# cpu.net
KiCad netlist of a schematic drawn in Altium Designer
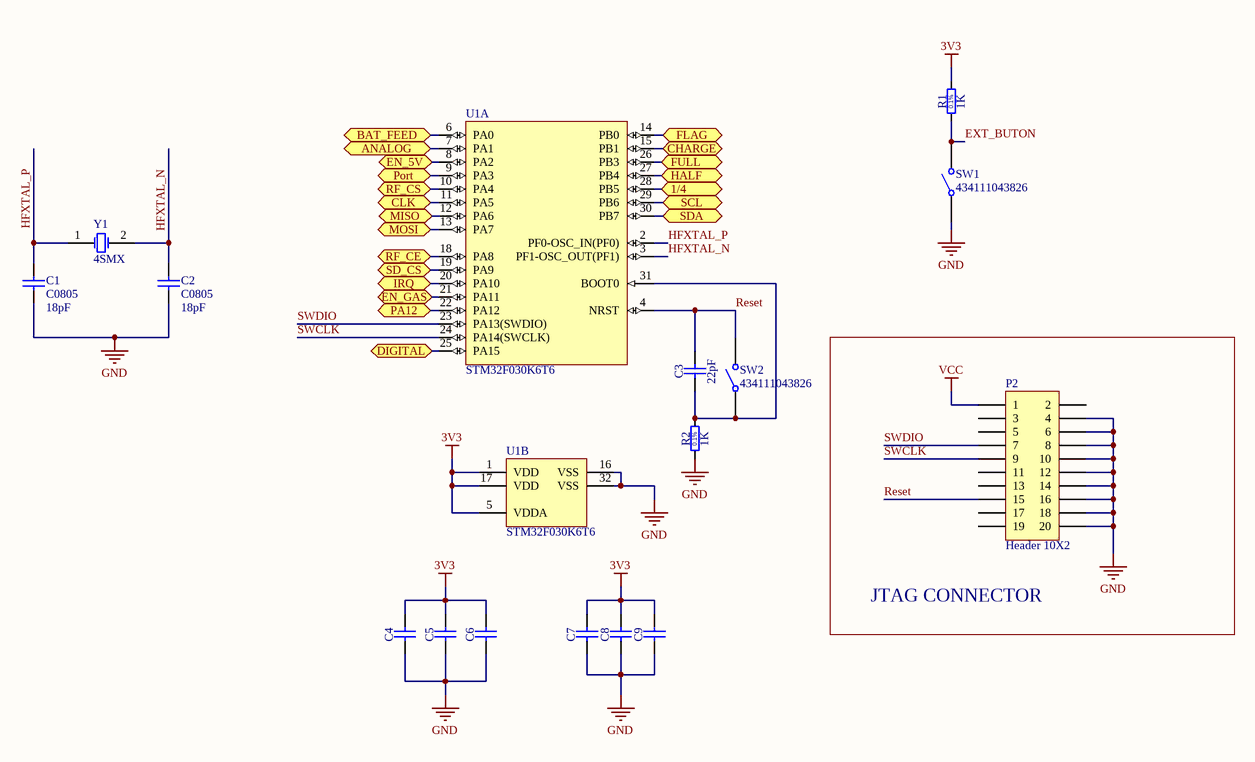
[diagram p0: cpu.SchDoc]

(export (version "E")
  (design (tool "Eeschema 10.0.6"))
  (components
    (comp (ref "C1")
      (value "C0805")
      (footprint "0805")
      (description "Ceramic Chip Capacitor - Standard")
      (fields (field (name "ALTIUM_VALUE") "18pF") (field (name "PUBLISHER") "Altium Limited"))
      (libsource (lib "KEMET Chip Capacitor") (part "C0805"))
    )
    (comp (ref "C2")
      (value "C0805")
      (footprint "0805")
      (description "Ceramic Chip Capacitor - Standard")
      (fields (field (name "ALTIUM_VALUE") "18pF") (field (name "PUBLISHER") "Altium Limited"))
      (libsource (lib "KEMET Chip Capacitor") (part "C0805"))
    )
    (comp (ref "C3")
      (value "22pF")
      (footprint "CAPC2012X135N")
      (description "Non-polarised capacitor")
      (fields
        (field (name "PART NUMBER") "CC0805_10NF_50V_10%_X7R")
        (field (name "VOLTAGE") "50V")
        (field (name "AUTHOR") "CERN DEM JLC")
      )
      (libsource (lib "Capacitors") (part "Capacitor - non polarized"))
    )
    (comp (ref "C4")
      (value "100nF")
      (footprint "CAPC2012X135N")
      (description "Non-polarised capacitor")
      (fields
        (field (name "PART NUMBER") "CC0805_1NF_50V_5%_X7R")
        (field (name "VOLTAGE") "50V")
        (field (name "AUTHOR") "CERN DEM JLC")
      )
      (libsource (lib "Capacitors") (part "Capacitor - non polarized"))
    )
    (comp (ref "C5")
      (value "100nF")
      (footprint "CAPC2012X135N")
      (description "Non-polarised capacitor")
      (fields
        (field (name "PART NUMBER") "CC0805_1NF_50V_5%_X7R")
        (field (name "VOLTAGE") "50V")
        (field (name "AUTHOR") "CERN DEM JLC")
      )
      (libsource (lib "Capacitors") (part "Capacitor - non polarized"))
    )
    (comp (ref "C6")
      (value "100nF")
      (footprint "CAPC2012X135N")
      (description "Non-polarised capacitor")
      (fields
        (field (name "PART NUMBER") "CC0805_1NF_50V_5%_X7R")
        (field (name "VOLTAGE") "50V")
        (field (name "AUTHOR") "CERN DEM JLC")
      )
      (libsource (lib "Capacitors") (part "Capacitor - non polarized"))
    )
    (comp (ref "C7")
      (value "100nF")
      (footprint "CAPC2012X135N")
      (description "Non-polarised capacitor")
      (fields
        (field (name "PART NUMBER") "CC0805_1NF_50V_5%_X7R")
        (field (name "VOLTAGE") "50V")
        (field (name "AUTHOR") "CERN DEM JLC")
      )
      (libsource (lib "Capacitors") (part "Capacitor - non polarized"))
    )
    (comp (ref "C8")
      (value "100nF")
      (footprint "CAPC2012X135N")
      (description "Non-polarised capacitor")
      (fields
        (field (name "PART NUMBER") "CC0805_1NF_50V_5%_X7R")
        (field (name "VOLTAGE") "50V")
        (field (name "AUTHOR") "CERN DEM JLC")
      )
      (libsource (lib "Capacitors") (part "Capacitor - non polarized"))
    )
    (comp (ref "C9")
      (value "100nF")
      (footprint "CAPC2012X135N")
      (description "Non-polarised capacitor")
      (fields
        (field (name "PART NUMBER") "CC0805_1NF_50V_5%_X7R")
        (field (name "VOLTAGE") "50V")
        (field (name "AUTHOR") "CERN DEM JLC")
      )
      (libsource (lib "Capacitors") (part "Capacitor - non polarized"))
    )
    (comp (ref "P2")
      (value "Header 10X2")
      (footprint "HDR2X10")
      (description "Header, 10-Pin, Dual row")
      (fields (field (name "PUBLISHER") "Altium Limited"))
      (libsource (lib "Miscellaneous Connectors") (part "Header 10X2"))
    )
    (comp (ref "R1")
      (value "1K")
      (footprint "RESC2012X60N")
      (description "Resistor - 0.1%")
      (fields
        (field (name "PART NUMBER") "R0805_1K1_0.1%_0.1W_10PPM")
        (field (name "POWER") "0.1W")
        (field (name "AUTHOR") "CERN DEM JLC")
      )
      (libsource (lib "Resistors") (part "Resistor - 0.1%"))
    )
    (comp (ref "R2")
      (value "1K")
      (footprint "RESC2012X60N")
      (description "Resistor - 0.1%")
      (fields
        (field (name "PART NUMBER") "R0805_1K1_0.1%_0.1W_10PPM")
        (field (name "POWER") "0.1W")
        (field (name "AUTHOR") "CERN DEM JLC")
      )
      (libsource (lib "Resistors") (part "Resistor - 0.1%"))
    )
    (comp (ref "SW1")
      (value "434111043826")
      (footprint "434111043826")
      (description "WS-TASV SMD Tact Switch 6.0X3.5 mm")
      (libsource (lib "WS-TASV SMD Tact Switch 6.0X3.5 mm") (part "434111043826"))
    )
    (comp (ref "SW2")
      (value "434111043826")
      (footprint "434111043826")
      (description "WS-TASV SMD Tact Switch 6.0X3.5 mm")
      (libsource (lib "WS-TASV SMD Tact Switch 6.0X3.5 mm") (part "434111043826"))
    )
    (comp (ref "U1")
      (value "STM32F030K6T6")
      (footprint "STM-LQFP32_N")
      (libsource (lib "STMicroelectronics STM32 F0") (part "STM32F030K6T6"))
    )
    (comp (ref "Y1")
      (value "4SMX")
      (footprint "4SMX")
      (description "Surface Mount Quartz Crystal")
      (fields (field (name "PUBLISHER") "Altium Limited"))
      (libsource (lib "C-MAC Crystal Oscillator") (part "4SMX"))
    )
  )
  (nets
    (net (code "1") (name "/1{slash}4") (class "Default")
      (node (ref "U1") (pin "28") (pinfunction "PB5_28") (pintype "bidirectional"))
    )
    (net (code "2") (name "/ANALOG") (class "Default")
      (node (ref "U1") (pin "7") (pinfunction "PA1_7") (pintype "bidirectional"))
    )
    (net (code "3") (name "/BAT_FEED") (class "Default")
      (node (ref "U1") (pin "6") (pinfunction "PA0_6") (pintype "bidirectional"))
    )
    (net (code "4") (name "/CHARGE") (class "Default")
      (node (ref "U1") (pin "15") (pinfunction "PB1_15") (pintype "bidirectional"))
    )
    (net (code "5") (name "/CLK") (class "Default")
      (node (ref "U1") (pin "11") (pinfunction "PA5_11") (pintype "bidirectional"))
    )
    (net (code "6") (name "/DIGITAL") (class "Default")
      (node (ref "U1") (pin "25") (pinfunction "PA15_25") (pintype "bidirectional"))
    )
    (net (code "7") (name "/EN_5V") (class "Default")
      (node (ref "U1") (pin "8") (pinfunction "PA2_8") (pintype "bidirectional"))
    )
    (net (code "8") (name "/EN_GAS") (class "Default")
      (node (ref "U1") (pin "21") (pinfunction "PA11_21") (pintype "bidirectional"))
    )
    (net (code "9") (name "/EXT_BUTON") (class "Default")
      (node (ref "R1") (pin "1") (pinfunction "1_1") (pintype "passive"))
      (node (ref "SW1") (pin "2") (pinfunction "2_2") (pintype "passive"))
    )
    (net (code "10") (name "/FLAG") (class "Default")
      (node (ref "U1") (pin "14") (pinfunction "PB0_14") (pintype "bidirectional"))
    )
    (net (code "11") (name "/FULL") (class "Default")
      (node (ref "U1") (pin "26") (pinfunction "PB3_26") (pintype "bidirectional"))
    )
    (net (code "12") (name "/HALF") (class "Default")
      (node (ref "U1") (pin "27") (pinfunction "PB4_27") (pintype "bidirectional"))
    )
    (net (code "13") (name "/HFXTAL_N") (class "Default")
      (node (ref "C2") (pin "2") (pinfunction "2_2") (pintype "passive"))
      (node (ref "U1") (pin "3") (pinfunction "PF1-OSC_OUT(PF1)_3") (pintype "bidirectional"))
      (node (ref "Y1") (pin "2") (pinfunction "OSC2_2") (pintype "passive"))
    )
    (net (code "14") (name "/HFXTAL_P") (class "Default")
      (node (ref "C1") (pin "2") (pinfunction "2_2") (pintype "passive"))
      (node (ref "U1") (pin "2") (pinfunction "PF0-OSC_IN(PF0)_2") (pintype "bidirectional"))
      (node (ref "Y1") (pin "1") (pinfunction "OSC1_1") (pintype "passive"))
    )
    (net (code "15") (name "/IRQ") (class "Default")
      (node (ref "U1") (pin "20") (pinfunction "PA10_20") (pintype "bidirectional"))
    )
    (net (code "16") (name "/MOSI") (class "Default")
      (node (ref "U1") (pin "13") (pinfunction "PA7_13") (pintype "bidirectional"))
    )
    (net (code "17") (name "/PA12") (class "Default")
      (node (ref "U1") (pin "22") (pinfunction "PA12_22") (pintype "bidirectional"))
    )
    (net (code "18") (name "/Port") (class "Default")
      (node (ref "U1") (pin "9") (pinfunction "PA3_9") (pintype "bidirectional"))
    )
    (net (code "19") (name "/RF_CE") (class "Default")
      (node (ref "U1") (pin "18") (pinfunction "PA8_18") (pintype "bidirectional"))
    )
    (net (code "20") (name "/RF_CS") (class "Default")
      (node (ref "U1") (pin "10") (pinfunction "PA4_10") (pintype "bidirectional"))
    )
    (net (code "21") (name "/Reset") (class "Default")
      (node (ref "C3") (pin "2") (pinfunction "2_2") (pintype "passive"))
      (node (ref "P2") (pin "15") (pinfunction "15_15") (pintype "passive"))
      (node (ref "SW2") (pin "2") (pinfunction "2_2") (pintype "passive"))
      (node (ref "U1") (pin "4") (pinfunction "NRST_4") (pintype "bidirectional"))
    )
    (net (code "22") (name "/SCL") (class "Default")
      (node (ref "U1") (pin "29") (pinfunction "PB6_29") (pintype "bidirectional"))
    )
    (net (code "23") (name "/SDA") (class "Default")
      (node (ref "U1") (pin "30") (pinfunction "PB7_30") (pintype "bidirectional"))
    )
    (net (code "24") (name "/SD_CS") (class "Default")
      (node (ref "U1") (pin "19") (pinfunction "PA9_19") (pintype "bidirectional"))
    )
    (net (code "25") (name "/SWCLK") (class "Default")
      (node (ref "P2") (pin "9") (pinfunction "9_9") (pintype "passive"))
      (node (ref "U1") (pin "24") (pinfunction "PA14(SWCLK)_24") (pintype "bidirectional"))
    )
    (net (code "26") (name "/SWDIO") (class "Default")
      (node (ref "P2") (pin "7") (pinfunction "7_7") (pintype "passive"))
      (node (ref "U1") (pin "23") (pinfunction "PA13(SWDIO)_23") (pintype "bidirectional"))
    )
    (net (code "27") (name "3V3") (class "Default")
      (node (ref "C4") (pin "2") (pinfunction "2_2") (pintype "passive"))
      (node (ref "C5") (pin "2") (pinfunction "2_2") (pintype "passive"))
      (node (ref "C6") (pin "2") (pinfunction "2_2") (pintype "passive"))
      (node (ref "C7") (pin "2") (pinfunction "2_2") (pintype "passive"))
      (node (ref "C8") (pin "2") (pinfunction "2_2") (pintype "passive"))
      (node (ref "C9") (pin "2") (pinfunction "2_2") (pintype "passive"))
      (node (ref "R1") (pin "2") (pinfunction "2_2") (pintype "passive"))
      (node (ref "U1") (pin "1") (pinfunction "VDD_1") (pintype "power_in"))
      (node (ref "U1") (pin "17") (pinfunction "VDD_17") (pintype "power_in"))
      (node (ref "U1") (pin "5") (pinfunction "VDDA_5") (pintype "power_in"))
    )
    (net (code "28") (name "GND") (class "Default")
      (node (ref "C1") (pin "1") (pinfunction "1_1") (pintype "passive"))
      (node (ref "C2") (pin "1") (pinfunction "1_1") (pintype "passive"))
      (node (ref "C4") (pin "1") (pinfunction "1_1") (pintype "passive"))
      (node (ref "C5") (pin "1") (pinfunction "1_1") (pintype "passive"))
      (node (ref "C6") (pin "1") (pinfunction "1_1") (pintype "passive"))
      (node (ref "C7") (pin "1") (pinfunction "1_1") (pintype "passive"))
      (node (ref "C8") (pin "1") (pinfunction "1_1") (pintype "passive"))
      (node (ref "C9") (pin "1") (pinfunction "1_1") (pintype "passive"))
      (node (ref "P2") (pin "10") (pinfunction "10_10") (pintype "passive"))
      (node (ref "P2") (pin "12") (pinfunction "12_12") (pintype "passive"))
      (node (ref "P2") (pin "14") (pinfunction "14_14") (pintype "passive"))
      (node (ref "P2") (pin "16") (pinfunction "16_16") (pintype "passive"))
      (node (ref "P2") (pin "18") (pinfunction "18_18") (pintype "passive"))
      (node (ref "P2") (pin "20") (pinfunction "20_20") (pintype "passive"))
      (node (ref "P2") (pin "4") (pinfunction "4_4") (pintype "passive"))
      (node (ref "P2") (pin "6") (pinfunction "6_6") (pintype "passive"))
      (node (ref "P2") (pin "8") (pinfunction "8_8") (pintype "passive"))
      (node (ref "R2") (pin "1") (pinfunction "1_1") (pintype "passive"))
      (node (ref "SW1") (pin "1") (pinfunction "1_1") (pintype "passive"))
      (node (ref "U1") (pin "16") (pinfunction "VSS_16") (pintype "power_in"))
      (node (ref "U1") (pin "32") (pinfunction "VSS_32") (pintype "power_in"))
    )
    (net (code "29") (name "Net-(U1A-BOOT0)") (class "Default")
      (node (ref "C3") (pin "1") (pinfunction "1_1") (pintype "passive"))
      (node (ref "R2") (pin "2") (pinfunction "2_2") (pintype "passive"))
      (node (ref "SW2") (pin "1") (pinfunction "1_1") (pintype "passive"))
      (node (ref "U1") (pin "31") (pinfunction "BOOT0_31") (pintype "input"))
    )
    (net (code "30") (name "VCC") (class "Default")
      (node (ref "P2") (pin "1") (pinfunction "1_1") (pintype "passive"))
    )
    (net (code "31") (name "unconnected-(P2-Pad2)") (class "Default")
      (node (ref "P2") (pin "2") (pinfunction "2_2") (pintype "passive"))
    )
    (net (code "32") (name "unconnected-(P2-Pad3)") (class "Default")
      (node (ref "P2") (pin "3") (pinfunction "3_3") (pintype "passive"))
    )
    (net (code "33") (name "unconnected-(P2-Pad5)") (class "Default")
      (node (ref "P2") (pin "5") (pinfunction "5_5") (pintype "passive"))
    )
    (net (code "34") (name "unconnected-(P2-Pad11)") (class "Default")
      (node (ref "P2") (pin "11") (pinfunction "11_11") (pintype "passive"))
    )
    (net (code "35") (name "unconnected-(P2-Pad13)") (class "Default")
      (node (ref "P2") (pin "13") (pinfunction "13_13") (pintype "passive"))
    )
    (net (code "36") (name "unconnected-(P2-Pad17)") (class "Default")
      (node (ref "P2") (pin "17") (pinfunction "17_17") (pintype "passive"))
    )
    (net (code "37") (name "unconnected-(P2-Pad19)") (class "Default")
      (node (ref "P2") (pin "19") (pinfunction "19_19") (pintype "passive"))
    )
    (net (code "38") (name "unconnected-(U1A-PA6-Pad12)") (class "Default")
      (node (ref "U1") (pin "12") (pinfunction "PA6_12") (pintype "bidirectional"))
    )
  )
)
